# ScaleBreakoutBoard2_0_3.net
KiCad netlist of a schematic drawn in EAGLE
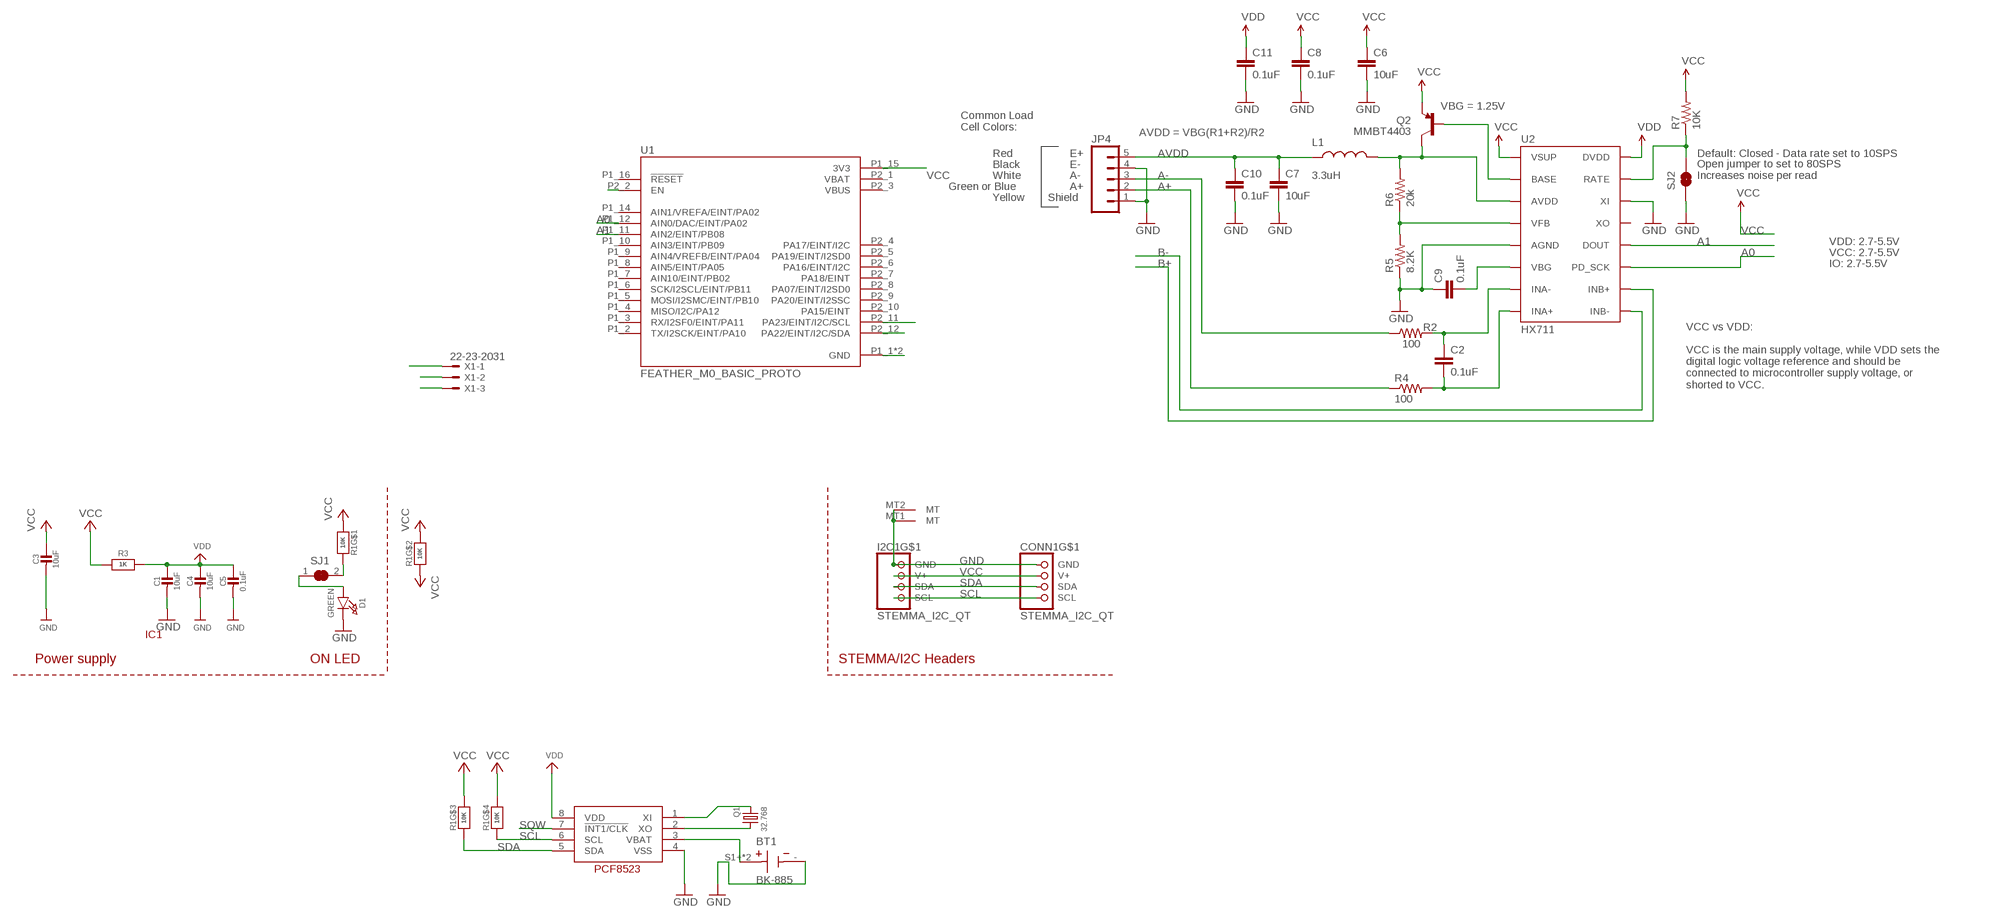
[diagram p0: schematic, sheet 1]

(export (version "E")
  (design (tool "Eeschema 10.0.6"))
  (components
    (comp (ref "BT1")
      (value "BK-885")
      (footprint "eagle-import:BAT_BK-885")
      (fields (field (name "MF") "MPD"))
      (libsource (lib "eagle-import") (part "BK-885"))
    )
    (comp (ref "C1")
      (value "10uF")
      (footprint "eagle-import:0805-NO")
      (libsource (lib "eagle-import") (part "CAP_CERAMIC0805-NOOUTLINE"))
    )
    (comp (ref "C2")
      (value "0.1uF")
      (footprint "eagle-import:0603-CAP")
      (libsource (lib "eagle-import") (part "0.1UF-25V-5%(0603)"))
    )
    (comp (ref "C3")
      (value "10uF")
      (footprint "eagle-import:0805-NO")
      (libsource (lib "eagle-import") (part "CAP_CERAMIC0805-NOOUTLINE"))
    )
    (comp (ref "C4")
      (value "10uF")
      (footprint "eagle-import:0805-NO")
      (libsource (lib "eagle-import") (part "CAP_CERAMIC0805-NOOUTLINE"))
    )
    (comp (ref "C5")
      (value "0.1uF")
      (footprint "eagle-import:0603-NO")
      (libsource (lib "eagle-import") (part "CAP_CERAMIC0603_NO"))
    )
    (comp (ref "C6")
      (value "10uF")
      (footprint "eagle-import:1210")
      (libsource (lib "eagle-import") (part "10UF50V20%(1210)"))
    )
    (comp (ref "C7")
      (value "10uF")
      (footprint "eagle-import:1210")
      (libsource (lib "eagle-import") (part "10UF50V20%(1210)"))
    )
    (comp (ref "C8")
      (value "0.1uF")
      (footprint "eagle-import:0603-CAP")
      (libsource (lib "eagle-import") (part "0.1UF-25V-5%(0603)"))
    )
    (comp (ref "C9")
      (value "0.1uF")
      (footprint "eagle-import:0603-CAP")
      (libsource (lib "eagle-import") (part "0.1UF-25V-5%(0603)"))
    )
    (comp (ref "C10")
      (value "0.1uF")
      (footprint "eagle-import:0603-CAP")
      (libsource (lib "eagle-import") (part "0.1UF-25V-5%(0603)"))
    )
    (comp (ref "C11")
      (value "0.1uF")
      (footprint "eagle-import:0603-CAP")
      (libsource (lib "eagle-import") (part "0.1UF-25V-5%(0603)"))
    )
    (comp (ref "CONN1")
      (value "STEMMA_I2C_QT")
      (footprint "eagle-import:JST_SH4")
      (libsource (lib "eagle-import") (part "STEMMA_I2C_QT"))
    )
    (comp (ref "D1")
      (value "GREEN")
      (footprint "eagle-import:CHIPLED_0603_NOOUTLINE")
      (libsource (lib "eagle-import") (part "LED0603_NOOUTLINE"))
    )
    (comp (ref "I2C1")
      (value "STEMMA_I2C_QT")
      (footprint "eagle-import:JST_SH4")
      (libsource (lib "eagle-import") (part "STEMMA_I2C_QT"))
    )
    (comp (ref "IC1")
      (value "RTC_PCF8523T")
      (footprint "eagle-import:SOIC8_150MIL")
      (libsource (lib "eagle-import") (part "RTC_PCF8523T"))
    )
    (comp (ref "JP4")
      (value "M05PTH")
      (footprint "eagle-import:1X05")
      (libsource (lib "eagle-import") (part "M05PTH"))
    )
    (comp (ref "L1")
      (value "3.3uH")
      (footprint "eagle-import:0805")
      (libsource (lib "eagle-import") (part "INDUCTOR0805-IND"))
    )
    (comp (ref "Q1")
      (value "32.768")
      (footprint "eagle-import:XTAL3215")
      (libsource (lib "eagle-import") (part "CRYSTAL_3215"))
    )
    (comp (ref "Q2")
      (value "MMBT4403")
      (footprint "eagle-import:SOT23-3")
      (libsource (lib "eagle-import") (part "TRANSISTOR_PNPMMBT4403"))
    )
    (comp (ref "R1")
      (value "10K")
      (footprint "eagle-import:RESPACK_4X0603")
      (libsource (lib "eagle-import") (part "RESISTOR_4PACK"))
    )
    (comp (ref "R2")
      (value "100")
      (footprint "eagle-import:0603-RES")
      (libsource (lib "eagle-import") (part "100OHM-1/10W-1%(0603)"))
    )
    (comp (ref "R3")
      (value "1K")
      (footprint "eagle-import:0603-NO")
      (libsource (lib "eagle-import") (part "RESISTOR_0603_NOOUT"))
    )
    (comp (ref "R4")
      (value "100")
      (footprint "eagle-import:0603-RES")
      (libsource (lib "eagle-import") (part "100OHM-1/10W-1%(0603)"))
    )
    (comp (ref "R5")
      (value "8.2K")
      (footprint "eagle-import:0603-RES")
      (libsource (lib "eagle-import") (part "8.2KOHM-1/10W-5%(0603)"))
    )
    (comp (ref "R6")
      (value "20k")
      (footprint "eagle-import:0603-RES")
      (libsource (lib "eagle-import") (part "20KOHM1/10W1%(0603)"))
    )
    (comp (ref "R7")
      (value "10K")
      (footprint "eagle-import:0603-RES")
      (libsource (lib "eagle-import") (part "10KOHM-1/10W-1%(0603)0603"))
    )
    (comp (ref "SJ1")
      (value "SOLDERJUMPER_CLOSED")
      (footprint "eagle-import:SOLDERJUMPER_CLOSEDWIRE")
      (libsource (lib "eagle-import") (part "SOLDERJUMPER_CLOSED"))
    )
    (comp (ref "SJ2")
      (value "JUMPER-PAD-2-NC_BY_TRACE")
      (footprint "eagle-import:PAD-JUMPER-2-NC_BY_TRACE_YES_SILK")
      (libsource (lib "eagle-import") (part "JUMPER-PAD-2-NC_BY_TRACE"))
    )
    (comp (ref "U1")
      (value "FEATHER_M0_BASIC_PROTO")
      (footprint "eagle-import:MODULE_FEATHER_M0_BASIC_PROTO")
      (fields (field (name "MF") "Adafruit Industries") (field (name "MP") "Feather M0 Basic Proto"))
      (libsource (lib "eagle-import") (part "FEATHER_M0_BASIC_PROTO"))
    )
    (comp (ref "U2")
      (value "HX711")
      (footprint "eagle-import:SO16")
      (libsource (lib "eagle-import") (part "HX711HX711"))
    )
    (comp (ref "X1")
      (value "22-23-2031")
      (footprint "eagle-import:22-23-2031")
      (fields (field (name "MF") "MOLEX"))
      (libsource (lib "eagle-import") (part "22-23-2031"))
    )
  )
  (nets
    (net (code "1") (name "/A+") (class "Default")
      (node (ref "JP4") (pin "2") (pinfunction "2_2") (pintype "passive"))
      (node (ref "R4") (pin "1") (pinfunction "1_1") (pintype "passive"))
    )
    (net (code "2") (name "/A-") (class "Default")
      (node (ref "JP4") (pin "3") (pinfunction "3_3") (pintype "passive"))
      (node (ref "R2") (pin "1") (pinfunction "1_1") (pintype "passive"))
    )
    (net (code "3") (name "/A0") (class "Default")
      (node (ref "U1") (pin "P1_12") (pinfunction "AIN0/DAC/EINT/PA02_P1_12") (pintype "bidirectional"))
      (node (ref "U2") (pin "11") (pinfunction "PD_SCK_11") (pintype "bidirectional"))
    )
    (net (code "4") (name "/A1") (class "Default")
      (node (ref "U1") (pin "P1_11") (pinfunction "AIN2/EINT/PB08_P1_11") (pintype "bidirectional"))
      (node (ref "U2") (pin "12") (pinfunction "DOUT_12") (pintype "bidirectional"))
    )
    (net (code "5") (name "/AVDD") (class "Default")
      (node (ref "C10") (pin "1") (pinfunction "1_1") (pintype "passive"))
      (node (ref "C7") (pin "1") (pinfunction "1_1") (pintype "passive"))
      (node (ref "JP4") (pin "5") (pinfunction "5_5") (pintype "passive"))
      (node (ref "L1") (pin "1") (pinfunction "1_1") (pintype "passive"))
    )
    (net (code "6") (name "/B+") (class "Default")
      (node (ref "U2") (pin "10") (pinfunction "INB+_10") (pintype "bidirectional"))
    )
    (net (code "7") (name "/B-") (class "Default")
      (node (ref "U2") (pin "9") (pinfunction "INB-_9") (pintype "bidirectional"))
    )
    (net (code "8") (name "/EN") (class "Default")
      (node (ref "U1") (pin "P2_2") (pinfunction "EN_P2_2") (pintype "input"))
      (node (ref "X1") (pin "3") (pinfunction "S_3") (pintype "passive"))
    )
    (net (code "9") (name "/SCL") (class "Default")
      (node (ref "CONN1") (pin "4") (pinfunction "SCL_4") (pintype "passive"))
      (node (ref "I2C1") (pin "4") (pinfunction "SCL_4") (pintype "passive"))
      (node (ref "IC1") (pin "6") (pinfunction "SCL_6") (pintype "bidirectional"))
      (node (ref "R1") (pin "4") (pinfunction "1_4") (pintype "passive"))
      (node (ref "U1") (pin "P2_11") (pinfunction "PA23/EINT/I2C/SCL_P2_11") (pintype "bidirectional"))
    )
    (net (code "10") (name "/SDA") (class "Default")
      (node (ref "CONN1") (pin "3") (pinfunction "SDA_3") (pintype "passive"))
      (node (ref "I2C1") (pin "3") (pinfunction "SDA_3") (pintype "passive"))
      (node (ref "IC1") (pin "5") (pinfunction "SDA_5") (pintype "bidirectional"))
      (node (ref "R1") (pin "3") (pinfunction "1_3") (pintype "passive"))
      (node (ref "U1") (pin "P2_12") (pinfunction "PA22/EINT/I2C/SDA_P2_12") (pintype "bidirectional"))
    )
    (net (code "11") (name "/SQW") (class "Default")
      (node (ref "IC1") (pin "7") (pinfunction "~{INT1/CLK}_7") (pintype "output"))
    )
    (net (code "12") (name "/VBAT") (class "Default")
      (node (ref "U1") (pin "P2_1") (pinfunction "VBAT_P2_1") (pintype "power_in"))
    )
    (net (code "13") (name "/VBUS") (class "Default")
      (node (ref "U1") (pin "P2_3") (pinfunction "VBUS_P2_3") (pintype "power_in"))
    )
    (net (code "14") (name "GND") (class "Default")
      (node (ref "BT1") (pin "-") (pinfunction "-_-") (pintype "passive"))
      (node (ref "C1") (pin "2") (pinfunction "2_2") (pintype "passive"))
      (node (ref "C10") (pin "2") (pinfunction "2_2") (pintype "passive"))
      (node (ref "C11") (pin "2") (pinfunction "2_2") (pintype "passive"))
      (node (ref "C3") (pin "2") (pinfunction "2_2") (pintype "passive"))
      (node (ref "C4") (pin "2") (pinfunction "2_2") (pintype "passive"))
      (node (ref "C5") (pin "2") (pinfunction "2_2") (pintype "passive"))
      (node (ref "C6") (pin "2") (pinfunction "2_2") (pintype "passive"))
      (node (ref "C7") (pin "2") (pinfunction "2_2") (pintype "passive"))
      (node (ref "C8") (pin "2") (pinfunction "2_2") (pintype "passive"))
      (node (ref "C9") (pin "1") (pinfunction "1_1") (pintype "passive"))
      (node (ref "CONN1") (pin "1") (pinfunction "GND_1") (pintype "passive"))
      (node (ref "D1") (pin "C") (pinfunction "C_C") (pintype "passive"))
      (node (ref "I2C1") (pin "1") (pinfunction "GND_1") (pintype "passive"))
      (node (ref "I2C1") (pin "MT1") (pinfunction "MT_MT1") (pintype "bidirectional"))
      (node (ref "I2C1") (pin "MT2") (pinfunction "MT_MT2") (pintype "bidirectional"))
      (node (ref "IC1") (pin "4") (pinfunction "VSS_4") (pintype "power_in"))
      (node (ref "JP4") (pin "1") (pinfunction "1_1") (pintype "passive"))
      (node (ref "JP4") (pin "4") (pinfunction "4_4") (pintype "passive"))
      (node (ref "R5") (pin "1") (pinfunction "1_1") (pintype "passive"))
      (node (ref "SJ2") (pin "1") (pinfunction "1_1") (pintype "passive"))
      (node (ref "U1") (pin "P1_1") (pinfunction "GND_P1_1") (pintype "power_in"))
      (node (ref "U1") (pin "P1_13") (pinfunction "GND_P1_13") (pintype "power_in"))
      (node (ref "U2") (pin "14") (pinfunction "XI_14") (pintype "bidirectional"))
      (node (ref "U2") (pin "5") (pinfunction "AGND_5") (pintype "bidirectional"))
      (node (ref "X1") (pin "1") (pinfunction "S_1") (pintype "passive"))
      (node (ref "X1") (pin "2") (pinfunction "S_2") (pintype "passive"))
    )
    (net (code "15") (name "Net-(D1-PadA)") (class "Default")
      (node (ref "D1") (pin "A") (pinfunction "A_A") (pintype "passive"))
      (node (ref "SJ1") (pin "1") (pinfunction "1_1") (pintype "passive"))
    )
    (net (code "16") (name "Net-(IC1-VBAT)") (class "Default")
      (node (ref "BT1") (pin "S1+") (pinfunction "+_S1+") (pintype "passive"))
      (node (ref "BT1") (pin "S2+") (pinfunction "+_S2+") (pintype "passive"))
      (node (ref "IC1") (pin "3") (pinfunction "VBAT_3") (pintype "power_in"))
    )
    (net (code "17") (name "Net-(IC1-XI)") (class "Default")
      (node (ref "IC1") (pin "1") (pinfunction "XI_1") (pintype "input"))
      (node (ref "Q1") (pin "P$1") (pinfunction "1_P$1") (pintype "passive"))
    )
    (net (code "18") (name "Net-(IC1-XO)") (class "Default")
      (node (ref "IC1") (pin "2") (pinfunction "XO_2") (pintype "output"))
      (node (ref "Q1") (pin "P$2") (pinfunction "2_P$2") (pintype "passive"))
    )
    (net (code "19") (name "Net-(Q2-B)") (class "Default")
      (node (ref "Q2") (pin "1") (pinfunction "B_1") (pintype "passive"))
      (node (ref "U2") (pin "2") (pinfunction "BASE_2") (pintype "bidirectional"))
    )
    (net (code "20") (name "Net-(Q2-C)") (class "Default")
      (node (ref "L1") (pin "2") (pinfunction "2_2") (pintype "passive"))
      (node (ref "Q2") (pin "3") (pinfunction "C_3") (pintype "passive"))
      (node (ref "R6") (pin "2") (pinfunction "2_2") (pintype "passive"))
      (node (ref "U2") (pin "3") (pinfunction "AVDD_3") (pintype "bidirectional"))
    )
    (net (code "21") (name "Net-(R1A-2)") (class "Default")
      (node (ref "R1") (pin "8") (pinfunction "2_8") (pintype "passive"))
      (node (ref "SJ1") (pin "2") (pinfunction "2_2") (pintype "passive"))
    )
    (net (code "22") (name "Net-(U2-INA+)") (class "Default")
      (node (ref "C2") (pin "2") (pinfunction "2_2") (pintype "passive"))
      (node (ref "R4") (pin "2") (pinfunction "2_2") (pintype "passive"))
      (node (ref "U2") (pin "8") (pinfunction "INA+_8") (pintype "bidirectional"))
    )
    (net (code "23") (name "Net-(U2-INA-)") (class "Default")
      (node (ref "C2") (pin "1") (pinfunction "1_1") (pintype "passive"))
      (node (ref "R2") (pin "2") (pinfunction "2_2") (pintype "passive"))
      (node (ref "U2") (pin "7") (pinfunction "INA-_7") (pintype "bidirectional"))
    )
    (net (code "24") (name "Net-(U2-RATE)") (class "Default")
      (node (ref "R7") (pin "1") (pinfunction "1_1") (pintype "passive"))
      (node (ref "SJ2") (pin "2") (pinfunction "2_2") (pintype "passive"))
      (node (ref "U2") (pin "15") (pinfunction "RATE_15") (pintype "bidirectional"))
    )
    (net (code "25") (name "Net-(U2-VBG)") (class "Default")
      (node (ref "C9") (pin "2") (pinfunction "2_2") (pintype "passive"))
      (node (ref "U2") (pin "6") (pinfunction "VBG_6") (pintype "bidirectional"))
    )
    (net (code "26") (name "Net-(U2-VFB)") (class "Default")
      (node (ref "R5") (pin "2") (pinfunction "2_2") (pintype "passive"))
      (node (ref "R6") (pin "1") (pinfunction "1_1") (pintype "passive"))
      (node (ref "U2") (pin "4") (pinfunction "VFB_4") (pintype "bidirectional"))
    )
    (net (code "27") (name "VCC") (class "Default")
      (node (ref "C3") (pin "1") (pinfunction "1_1") (pintype "passive"))
      (node (ref "C6") (pin "1") (pinfunction "1_1") (pintype "passive"))
      (node (ref "C8") (pin "1") (pinfunction "1_1") (pintype "passive"))
      (node (ref "CONN1") (pin "2") (pinfunction "V+_2") (pintype "passive"))
      (node (ref "I2C1") (pin "2") (pinfunction "V+_2") (pintype "passive"))
      (node (ref "Q2") (pin "2") (pinfunction "E_2") (pintype "passive"))
      (node (ref "R1") (pin "1") (pinfunction "1_1") (pintype "passive"))
      (node (ref "R1") (pin "2") (pinfunction "1_2") (pintype "passive"))
      (node (ref "R1") (pin "5") (pinfunction "2_5") (pintype "passive"))
      (node (ref "R1") (pin "6") (pinfunction "2_6") (pintype "passive"))
      (node (ref "R1") (pin "7") (pinfunction "2_7") (pintype "passive"))
      (node (ref "R3") (pin "1") (pinfunction "1_1") (pintype "passive"))
      (node (ref "R7") (pin "2") (pinfunction "2_2") (pintype "passive"))
      (node (ref "U1") (pin "P1_15") (pinfunction "3V3_P1_15") (pintype "power_in"))
      (node (ref "U2") (pin "1") (pinfunction "VSUP_1") (pintype "bidirectional"))
    )
    (net (code "28") (name "VDD") (class "Default")
      (node (ref "C1") (pin "1") (pinfunction "1_1") (pintype "passive"))
      (node (ref "C11") (pin "1") (pinfunction "1_1") (pintype "passive"))
      (node (ref "C4") (pin "1") (pinfunction "1_1") (pintype "passive"))
      (node (ref "C5") (pin "1") (pinfunction "1_1") (pintype "passive"))
      (node (ref "IC1") (pin "8") (pinfunction "VDD_8") (pintype "power_in"))
      (node (ref "R3") (pin "2") (pinfunction "2_2") (pintype "passive"))
      (node (ref "U2") (pin "16") (pinfunction "DVDD_16") (pintype "bidirectional"))
    )
    (net (code "29") (name "unconnected-(U1-AIN1{slash}VREFA{slash}EINT{slash}PA02-PadP1_14)") (class "Default")
      (node (ref "U1") (pin "P1_14") (pinfunction "AIN1/VREFA/EINT/PA02_P1_14") (pintype "bidirectional"))
    )
    (net (code "30") (name "unconnected-(U1-AIN3{slash}EINT{slash}PB09-PadP1_10)") (class "Default")
      (node (ref "U1") (pin "P1_10") (pinfunction "AIN3/EINT/PB09_P1_10") (pintype "bidirectional"))
    )
    (net (code "31") (name "unconnected-(U1-AIN4{slash}VREFB{slash}EINT{slash}PA04-PadP1_9)") (class "Default")
      (node (ref "U1") (pin "P1_9") (pinfunction "AIN4/VREFB/EINT/PA04_P1_9") (pintype "bidirectional"))
    )
    (net (code "32") (name "unconnected-(U1-AIN5{slash}EINT{slash}PA05-PadP1_8)") (class "Default")
      (node (ref "U1") (pin "P1_8") (pinfunction "AIN5/EINT/PA05_P1_8") (pintype "bidirectional"))
    )
    (net (code "33") (name "unconnected-(U1-AIN10{slash}EINT{slash}PB02-PadP1_7)") (class "Default")
      (node (ref "U1") (pin "P1_7") (pinfunction "AIN10/EINT/PB02_P1_7") (pintype "bidirectional"))
    )
    (net (code "34") (name "unconnected-(U1-MISO{slash}I2C{slash}PA12-PadP1_4)") (class "Default")
      (node (ref "U1") (pin "P1_4") (pinfunction "MISO/I2C/PA12_P1_4") (pintype "bidirectional"))
    )
    (net (code "35") (name "unconnected-(U1-MOSI{slash}I2SMC{slash}EINT{slash}PB10-PadP1_5)") (class "Default")
      (node (ref "U1") (pin "P1_5") (pinfunction "MOSI/I2SMC/EINT/PB10_P1_5") (pintype "bidirectional"))
    )
    (net (code "36") (name "unconnected-(U1-PA07{slash}EINT{slash}I2SD0-PadP2_8)") (class "Default")
      (node (ref "U1") (pin "P2_8") (pinfunction "PA07/EINT/I2SD0_P2_8") (pintype "bidirectional"))
    )
    (net (code "37") (name "unconnected-(U1-PA15{slash}EINT-PadP2_10)") (class "Default")
      (node (ref "U1") (pin "P2_10") (pinfunction "PA15/EINT_P2_10") (pintype "bidirectional"))
    )
    (net (code "38") (name "unconnected-(U1-PA16{slash}EINT{slash}I2C-PadP2_6)") (class "Default")
      (node (ref "U1") (pin "P2_6") (pinfunction "PA16/EINT/I2C_P2_6") (pintype "bidirectional"))
    )
    (net (code "39") (name "unconnected-(U1-PA17{slash}EINT{slash}I2C-PadP2_4)") (class "Default")
      (node (ref "U1") (pin "P2_4") (pinfunction "PA17/EINT/I2C_P2_4") (pintype "bidirectional"))
    )
    (net (code "40") (name "unconnected-(U1-PA18{slash}EINT-PadP2_7)") (class "Default")
      (node (ref "U1") (pin "P2_7") (pinfunction "PA18/EINT_P2_7") (pintype "bidirectional"))
    )
    (net (code "41") (name "unconnected-(U1-PA19{slash}EINT{slash}I2SD0-PadP2_5)") (class "Default")
      (node (ref "U1") (pin "P2_5") (pinfunction "PA19/EINT/I2SD0_P2_5") (pintype "bidirectional"))
    )
    (net (code "42") (name "unconnected-(U1-PA20{slash}EINT{slash}I2SSC-PadP2_9)") (class "Default")
      (node (ref "U1") (pin "P2_9") (pinfunction "PA20/EINT/I2SSC_P2_9") (pintype "bidirectional"))
    )
    (net (code "43") (name "unconnected-(U1-RX{slash}I2SF0{slash}EINT{slash}PA11-PadP1_3)") (class "Default")
      (node (ref "U1") (pin "P1_3") (pinfunction "RX/I2SF0/EINT/PA11_P1_3") (pintype "bidirectional"))
    )
    (net (code "44") (name "unconnected-(U1-SCK{slash}I2SCL{slash}EINT{slash}PB11-PadP1_6)") (class "Default")
      (node (ref "U1") (pin "P1_6") (pinfunction "SCK/I2SCL/EINT/PB11_P1_6") (pintype "bidirectional"))
    )
    (net (code "45") (name "unconnected-(U1-TX{slash}I2SCK{slash}EINT{slash}PA10-PadP1_2)") (class "Default")
      (node (ref "U1") (pin "P1_2") (pinfunction "TX/I2SCK/EINT/PA10_P1_2") (pintype "bidirectional"))
    )
    (net (code "46") (name "unconnected-(U1-~{RESET}-PadP1_16)") (class "Default")
      (node (ref "U1") (pin "P1_16") (pinfunction "~{RESET}_P1_16") (pintype "input"))
    )
    (net (code "47") (name "unconnected-(U2-XO-Pad13)") (class "Default")
      (node (ref "U2") (pin "13") (pinfunction "XO_13") (pintype "bidirectional"))
    )
  )
)
